# ADIO.net
KiCad netlist of a schematic drawn in Altium Designer
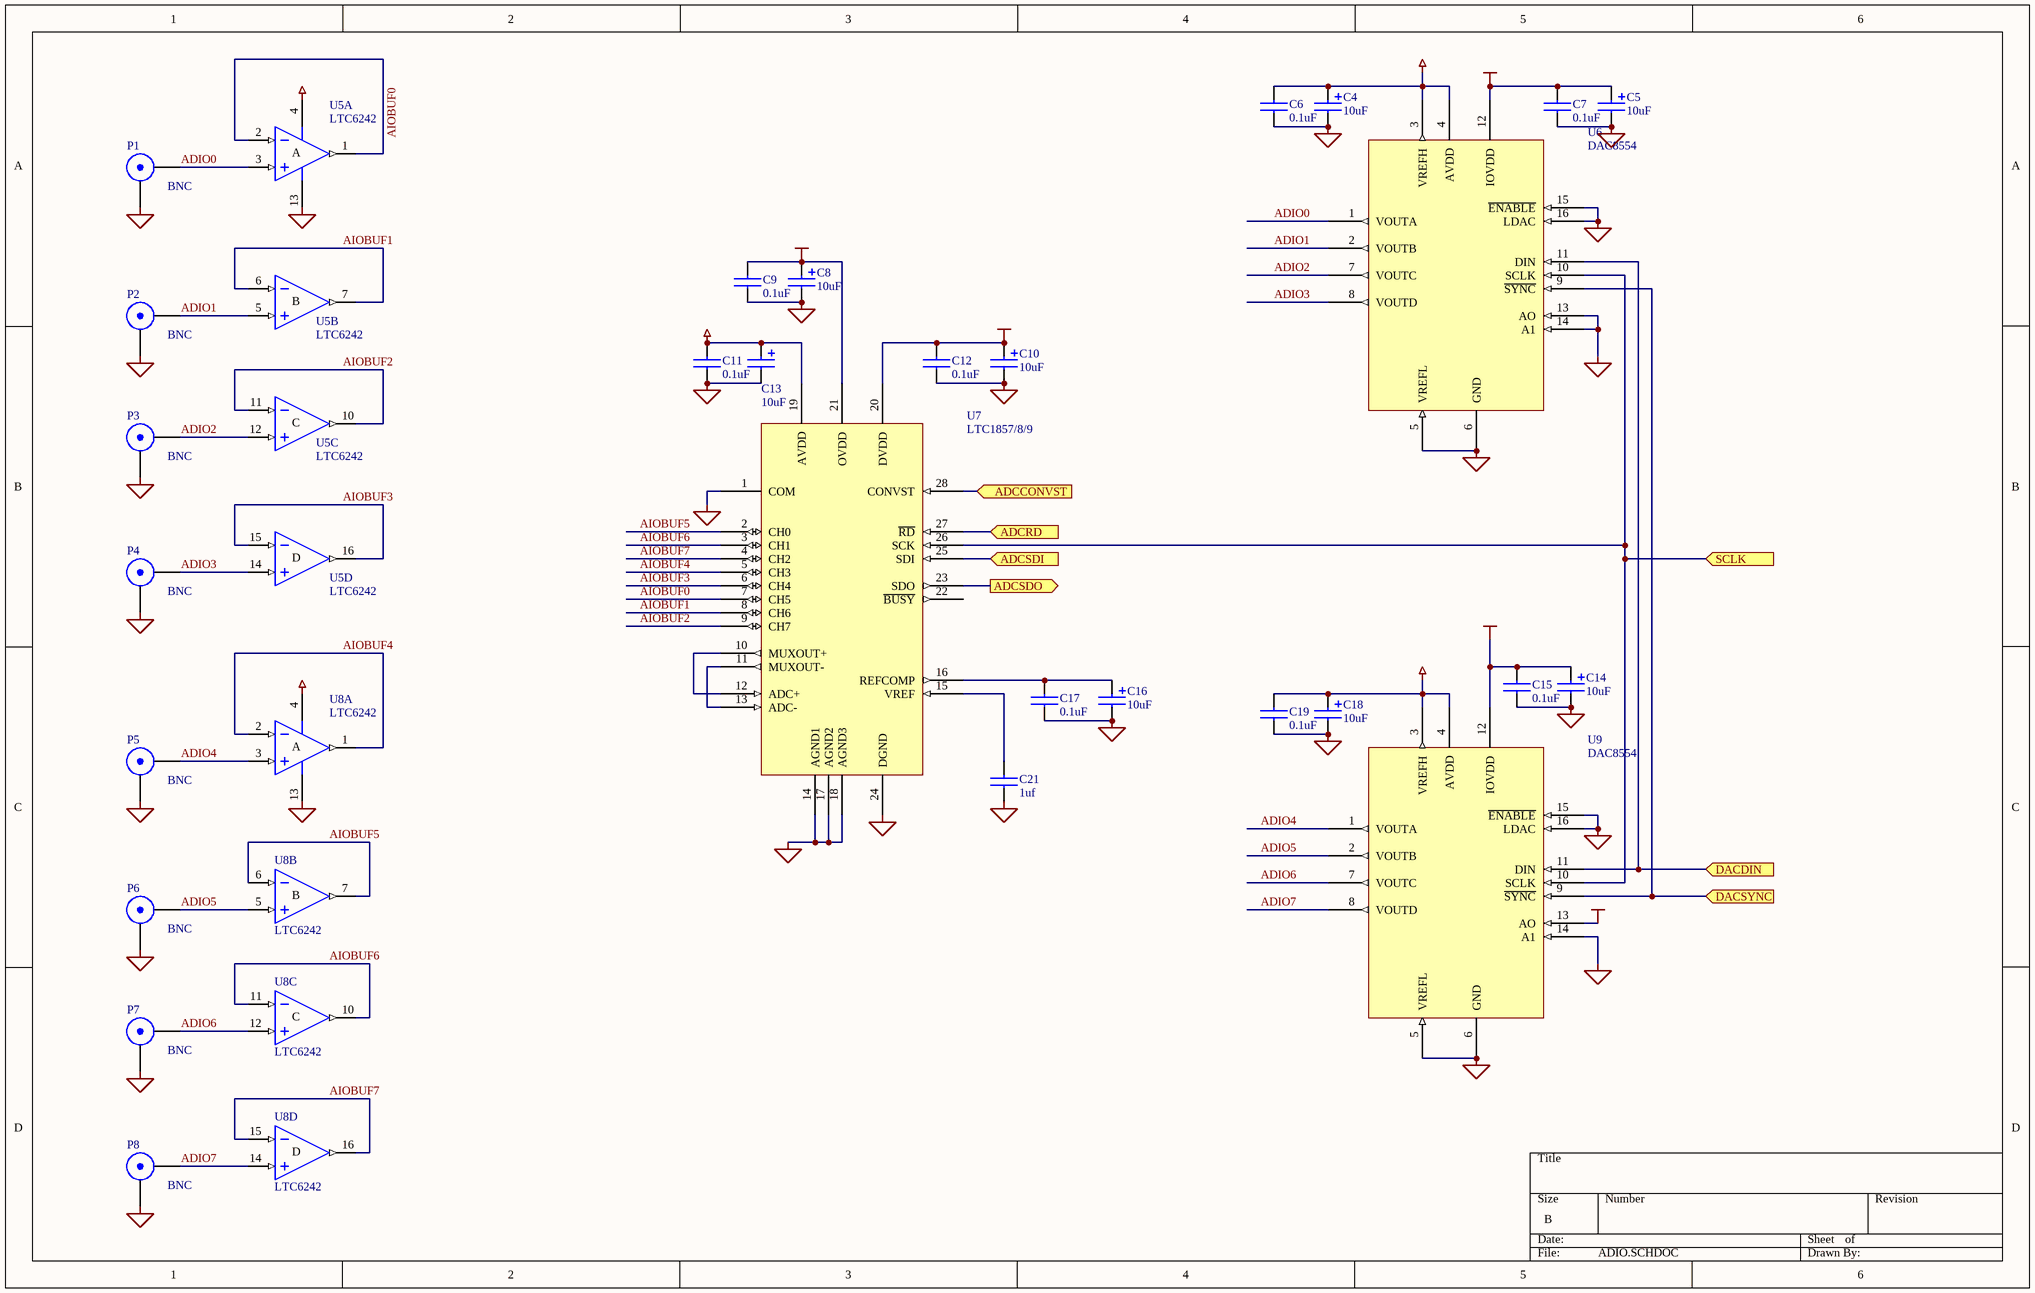
[diagram p0: ADIO.SCHDOC]

(export (version "E")
  (design (tool "Eeschema 10.0.6"))
  (components
    (comp (ref "C4")
      (value "10uF")
      (footprint "3216")
      (description "Standard Capacitor")
      (fields (field (name "Comment") "POLCAP"))
      (libsource (lib "parts") (part "POLCAP"))
    )
    (comp (ref "C5")
      (value "10uF")
      (footprint "3216")
      (description "Standard Capacitor")
      (fields (field (name "Comment") "POLCAP"))
      (libsource (lib "parts") (part "POLCAP"))
    )
    (comp (ref "C6")
      (value "0.1uF")
      (footprint "0603")
      (description "Standard Capacitor")
      (fields (field (name "Comment") "CAPACITOR"))
      (libsource (lib "parts") (part "CAPACITOR"))
    )
    (comp (ref "C7")
      (value "0.1uF")
      (footprint "0603")
      (description "Standard Capacitor")
      (fields (field (name "Comment") "CAPACITOR"))
      (libsource (lib "parts") (part "CAPACITOR"))
    )
    (comp (ref "C8")
      (value "10uF")
      (footprint "3216")
      (description "Standard Capacitor")
      (fields (field (name "Comment") "POLCAP"))
      (libsource (lib "parts") (part "POLCAP"))
    )
    (comp (ref "C9")
      (value "0.1uF")
      (footprint "0603")
      (description "Standard Capacitor")
      (fields (field (name "Comment") "CAPACITOR"))
      (libsource (lib "parts") (part "CAPACITOR"))
    )
    (comp (ref "C10")
      (value "10uF")
      (footprint "3216")
      (description "Standard Capacitor")
      (fields (field (name "Comment") "POLCAP"))
      (libsource (lib "parts") (part "POLCAP"))
    )
    (comp (ref "C11")
      (value "0.1uF")
      (footprint "0603")
      (description "Standard Capacitor")
      (fields (field (name "Comment") "CAPACITOR"))
      (libsource (lib "parts") (part "CAPACITOR"))
    )
    (comp (ref "C12")
      (value "0.1uF")
      (footprint "0603")
      (description "Standard Capacitor")
      (fields (field (name "Comment") "CAPACITOR"))
      (libsource (lib "parts") (part "CAPACITOR"))
    )
    (comp (ref "C13")
      (value "10uF")
      (footprint "3216")
      (description "Standard Capacitor")
      (fields (field (name "Comment") "POLCAP"))
      (libsource (lib "parts") (part "POLCAP"))
    )
    (comp (ref "C14")
      (value "10uF")
      (footprint "3216")
      (description "Standard Capacitor")
      (fields (field (name "Comment") "POLCAP"))
      (libsource (lib "parts") (part "POLCAP"))
    )
    (comp (ref "C15")
      (value "0.1uF")
      (footprint "0603")
      (description "Standard Capacitor")
      (fields (field (name "Comment") "CAPACITOR"))
      (libsource (lib "parts") (part "CAPACITOR"))
    )
    (comp (ref "C16")
      (value "10uF")
      (footprint "3216")
      (description "Standard Capacitor")
      (fields (field (name "Comment") "POLCAP"))
      (libsource (lib "parts") (part "POLCAP"))
    )
    (comp (ref "C17")
      (value "0.1uF")
      (footprint "0603")
      (description "Standard Capacitor")
      (fields (field (name "Comment") "CAPACITOR"))
      (libsource (lib "parts") (part "CAPACITOR"))
    )
    (comp (ref "C18")
      (value "10uF")
      (footprint "3216")
      (description "Standard Capacitor")
      (fields (field (name "Comment") "POLCAP"))
      (libsource (lib "parts") (part "POLCAP"))
    )
    (comp (ref "C19")
      (value "0.1uF")
      (footprint "0603")
      (description "Standard Capacitor")
      (fields (field (name "Comment") "CAPACITOR"))
      (libsource (lib "parts") (part "CAPACITOR"))
    )
    (comp (ref "C21")
      (value "1uf")
      (footprint "0603")
      (description "Standard Capacitor")
      (fields (field (name "Comment") "CAPACITOR"))
      (libsource (lib "parts") (part "CAPACITOR"))
    )
    (comp (ref "P1")
      (value "BNC")
      (footprint "Vertical BNC 227699-1")
      (description "BNC Elbow Connector")
      (fields (field (name "MANUFACTURER") "Generic Components") (field (name "PUBLISHER") "Altium Limited"))
      (libsource (lib "Miscellaneous Connectors") (part "BNC"))
    )
    (comp (ref "P2")
      (value "BNC")
      (footprint "Vertical BNC 227699-1")
      (description "BNC Elbow Connector")
      (fields (field (name "MANUFACTURER") "Generic Components") (field (name "PUBLISHER") "Altium Limited"))
      (libsource (lib "Miscellaneous Connectors") (part "BNC"))
    )
    (comp (ref "P3")
      (value "BNC")
      (footprint "Vertical BNC 227699-1")
      (description "BNC Elbow Connector")
      (fields (field (name "MANUFACTURER") "Generic Components") (field (name "PUBLISHER") "Altium Limited"))
      (libsource (lib "Miscellaneous Connectors") (part "BNC"))
    )
    (comp (ref "P4")
      (value "BNC")
      (footprint "Vertical BNC 227699-1")
      (description "BNC Elbow Connector")
      (fields (field (name "MANUFACTURER") "Generic Components") (field (name "PUBLISHER") "Altium Limited"))
      (libsource (lib "Miscellaneous Connectors") (part "BNC"))
    )
    (comp (ref "P5")
      (value "BNC")
      (footprint "Vertical BNC 227699-1")
      (description "BNC Elbow Connector")
      (fields (field (name "MANUFACTURER") "Generic Components") (field (name "PUBLISHER") "Altium Limited"))
      (libsource (lib "Miscellaneous Connectors") (part "BNC"))
    )
    (comp (ref "P6")
      (value "BNC")
      (footprint "Vertical BNC 227699-1")
      (description "BNC Elbow Connector")
      (fields (field (name "MANUFACTURER") "Generic Components") (field (name "PUBLISHER") "Altium Limited"))
      (libsource (lib "Miscellaneous Connectors") (part "BNC"))
    )
    (comp (ref "P7")
      (value "BNC")
      (footprint "Vertical BNC 227699-1")
      (description "BNC Elbow Connector")
      (fields (field (name "MANUFACTURER") "Generic Components") (field (name "PUBLISHER") "Altium Limited"))
      (libsource (lib "Miscellaneous Connectors") (part "BNC"))
    )
    (comp (ref "P8")
      (value "BNC")
      (footprint "Vertical BNC 227699-1")
      (description "BNC Elbow Connector")
      (fields (field (name "MANUFACTURER") "Generic Components") (field (name "PUBLISHER") "Altium Limited"))
      (libsource (lib "Miscellaneous Connectors") (part "BNC"))
    )
    (comp (ref "U5")
      (value "LTC6242")
      (footprint "LTCDHC-16")
      (description "Quad 18 Mhz, Low Noise, Rail-to-Rail CMOS Op-Amp")
      (fields (field (name "PUBLISHER") "Altium Limited"))
      (libsource (lib "parts") (part "LTC6242"))
    )
    (comp (ref "U6")
      (value "DAC8554")
      (footprint "TSSO5x6-G16")
      (description "TI 16-bit quad chan Voltage Output DAC")
      (libsource (lib "parts") (part "DAC8554"))
    )
    (comp (ref "U7")
      (value "LTC1857/8/9")
      (footprint "LTI_G_TSSOP")
      (description "LTC 8-channel 12, 14, 16 100ksps ADC")
      (libsource (lib "parts") (part "LTC1859"))
    )
    (comp (ref "U8")
      (value "LTC6242")
      (footprint "LTCDHC-16")
      (description "Quad 18 Mhz, Low Noise, Rail-to-Rail CMOS Op-Amp")
      (fields (field (name "PUBLISHER") "Altium Limited"))
      (libsource (lib "parts") (part "LTC6242"))
    )
    (comp (ref "U9")
      (value "DAC8554")
      (footprint "TSSO5x6-G16")
      (description "TI 16-bit quad chan Voltage Output DAC")
      (libsource (lib "parts") (part "DAC8554"))
    )
  )
  (nets
    (net (code "1") (name "+5VCC") (class "Default")
      (node (ref "C10") (pin "1") (pintype "passive"))
      (node (ref "C12") (pin "1") (pintype "passive"))
      (node (ref "U7") (pin "20") (pinfunction "DVDD_20") (pintype "power_in"))
    )
    (net (code "2") (name "/ADCCONVST") (class "Default")
      (node (ref "U7") (pin "28") (pinfunction "CONVST_28") (pintype "input"))
    )
    (net (code "3") (name "/ADCRD") (class "Default")
      (node (ref "U7") (pin "27") (pinfunction "~{RD}_27") (pintype "input"))
    )
    (net (code "4") (name "/ADCSDI") (class "Default")
      (node (ref "U7") (pin "25") (pinfunction "SDI_25") (pintype "input"))
    )
    (net (code "5") (name "/ADCSDO") (class "Default")
      (node (ref "U7") (pin "23") (pinfunction "SDO_23") (pintype "output"))
    )
    (net (code "6") (name "/ADIO0") (class "Default")
      (node (ref "P1") (pin "1") (pinfunction "X_1") (pintype "passive"))
      (node (ref "U5") (pin "3") (pinfunction "IN+_3") (pintype "input"))
      (node (ref "U6") (pin "1") (pinfunction "VOUTA_1") (pintype "output"))
    )
    (net (code "7") (name "/ADIO1") (class "Default")
      (node (ref "P2") (pin "1") (pinfunction "X_1") (pintype "passive"))
      (node (ref "U5") (pin "5") (pinfunction "IN+_5") (pintype "input"))
      (node (ref "U6") (pin "2") (pinfunction "VOUTB_2") (pintype "output"))
    )
    (net (code "8") (name "/ADIO2") (class "Default")
      (node (ref "P3") (pin "1") (pinfunction "X_1") (pintype "passive"))
      (node (ref "U5") (pin "12") (pinfunction "IN+_12") (pintype "input"))
      (node (ref "U6") (pin "7") (pinfunction "VOUTC_7") (pintype "output"))
    )
    (net (code "9") (name "/ADIO3") (class "Default")
      (node (ref "P4") (pin "1") (pinfunction "X_1") (pintype "passive"))
      (node (ref "U5") (pin "14") (pinfunction "IN+_14") (pintype "input"))
      (node (ref "U6") (pin "8") (pinfunction "VOUTD_8") (pintype "output"))
    )
    (net (code "10") (name "/ADIO4") (class "Default")
      (node (ref "P5") (pin "1") (pinfunction "X_1") (pintype "passive"))
      (node (ref "U8") (pin "3") (pinfunction "IN+_3") (pintype "input"))
      (node (ref "U9") (pin "1") (pinfunction "VOUTA_1") (pintype "output"))
    )
    (net (code "11") (name "/ADIO5") (class "Default")
      (node (ref "P6") (pin "1") (pinfunction "X_1") (pintype "passive"))
      (node (ref "U8") (pin "5") (pinfunction "IN+_5") (pintype "input"))
      (node (ref "U9") (pin "2") (pinfunction "VOUTB_2") (pintype "output"))
    )
    (net (code "12") (name "/ADIO6") (class "Default")
      (node (ref "P7") (pin "1") (pinfunction "X_1") (pintype "passive"))
      (node (ref "U8") (pin "12") (pinfunction "IN+_12") (pintype "input"))
      (node (ref "U9") (pin "7") (pinfunction "VOUTC_7") (pintype "output"))
    )
    (net (code "13") (name "/ADIO7") (class "Default")
      (node (ref "P8") (pin "1") (pinfunction "X_1") (pintype "passive"))
      (node (ref "U8") (pin "14") (pinfunction "IN+_14") (pintype "input"))
      (node (ref "U9") (pin "8") (pinfunction "VOUTD_8") (pintype "output"))
    )
    (net (code "14") (name "/AIOBUF0") (class "Default")
      (node (ref "U5") (pin "1") (pinfunction "OUT_1") (pintype "output"))
      (node (ref "U5") (pin "2") (pinfunction "IN-_2") (pintype "input"))
      (node (ref "U7") (pin "7") (pinfunction "CH5_7") (pintype "bidirectional"))
    )
    (net (code "15") (name "/AIOBUF1") (class "Default")
      (node (ref "U5") (pin "6") (pinfunction "IN-_6") (pintype "input"))
      (node (ref "U5") (pin "7") (pinfunction "OUT_7") (pintype "output"))
      (node (ref "U7") (pin "8") (pinfunction "CH6_8") (pintype "bidirectional"))
    )
    (net (code "16") (name "/AIOBUF2") (class "Default")
      (node (ref "U5") (pin "10") (pinfunction "OUT_10") (pintype "output"))
      (node (ref "U5") (pin "11") (pinfunction "IN-_11") (pintype "input"))
      (node (ref "U7") (pin "9") (pinfunction "CH7_9") (pintype "bidirectional"))
    )
    (net (code "17") (name "/AIOBUF3") (class "Default")
      (node (ref "U5") (pin "15") (pinfunction "IN-_15") (pintype "input"))
      (node (ref "U5") (pin "16") (pinfunction "OUT_16") (pintype "output"))
      (node (ref "U7") (pin "6") (pinfunction "CH4_6") (pintype "bidirectional"))
    )
    (net (code "18") (name "/AIOBUF4") (class "Default")
      (node (ref "U7") (pin "5") (pinfunction "CH3_5") (pintype "bidirectional"))
      (node (ref "U8") (pin "1") (pinfunction "OUT_1") (pintype "output"))
      (node (ref "U8") (pin "2") (pinfunction "IN-_2") (pintype "input"))
    )
    (net (code "19") (name "/AIOBUF5") (class "Default")
      (node (ref "U7") (pin "2") (pinfunction "CH0_2") (pintype "bidirectional"))
      (node (ref "U8") (pin "6") (pinfunction "IN-_6") (pintype "input"))
      (node (ref "U8") (pin "7") (pinfunction "OUT_7") (pintype "output"))
    )
    (net (code "20") (name "/AIOBUF6") (class "Default")
      (node (ref "U7") (pin "3") (pinfunction "CH1_3") (pintype "bidirectional"))
      (node (ref "U8") (pin "10") (pinfunction "OUT_10") (pintype "output"))
      (node (ref "U8") (pin "11") (pinfunction "IN-_11") (pintype "input"))
    )
    (net (code "21") (name "/AIOBUF7") (class "Default")
      (node (ref "U7") (pin "4") (pinfunction "CH2_4") (pintype "bidirectional"))
      (node (ref "U8") (pin "15") (pinfunction "IN-_15") (pintype "input"))
      (node (ref "U8") (pin "16") (pinfunction "OUT_16") (pintype "output"))
    )
    (net (code "22") (name "/DACDIN") (class "Default")
      (node (ref "U6") (pin "11") (pinfunction "DIN_11") (pintype "input"))
      (node (ref "U9") (pin "11") (pinfunction "DIN_11") (pintype "input"))
    )
    (net (code "23") (name "/DACSYNC") (class "Default")
      (node (ref "U6") (pin "9") (pinfunction "~{SYNC}_9") (pintype "input"))
      (node (ref "U9") (pin "9") (pinfunction "~{SYNC}_9") (pintype "input"))
    )
    (net (code "24") (name "/SCLK") (class "Default")
      (node (ref "U6") (pin "10") (pinfunction "SCLK_10") (pintype "input"))
      (node (ref "U7") (pin "26") (pinfunction "SCK_26") (pintype "input"))
      (node (ref "U9") (pin "10") (pinfunction "SCLK_10") (pintype "input"))
    )
    (net (code "25") (name "AVDD") (class "Default")
      (node (ref "C11") (pin "1") (pintype "passive"))
      (node (ref "C13") (pin "1") (pintype "passive"))
      (node (ref "C18") (pin "1") (pintype "passive"))
      (node (ref "C19") (pin "1") (pintype "passive"))
      (node (ref "C4") (pin "1") (pintype "passive"))
      (node (ref "C6") (pin "1") (pintype "passive"))
      (node (ref "U5") (pin "4") (pinfunction "V+_4") (pintype "power_in"))
      (node (ref "U6") (pin "3") (pinfunction "VREFH_3") (pintype "output"))
      (node (ref "U6") (pin "4") (pinfunction "AVDD_4") (pintype "power_in"))
      (node (ref "U7") (pin "19") (pinfunction "AVDD_19") (pintype "power_in"))
      (node (ref "U8") (pin "4") (pinfunction "V+_4") (pintype "power_in"))
      (node (ref "U9") (pin "3") (pinfunction "VREFH_3") (pintype "output"))
      (node (ref "U9") (pin "4") (pinfunction "AVDD_4") (pintype "power_in"))
    )
    (net (code "26") (name "GND") (class "Default")
      (node (ref "C10") (pin "2") (pintype "passive"))
      (node (ref "C11") (pin "2") (pintype "passive"))
      (node (ref "C12") (pin "2") (pintype "passive"))
      (node (ref "C13") (pin "2") (pintype "passive"))
      (node (ref "C14") (pin "2") (pintype "passive"))
      (node (ref "C15") (pin "2") (pintype "passive"))
      (node (ref "C16") (pin "2") (pintype "passive"))
      (node (ref "C17") (pin "2") (pintype "passive"))
      (node (ref "C18") (pin "2") (pintype "passive"))
      (node (ref "C19") (pin "2") (pintype "passive"))
      (node (ref "C21") (pin "2") (pintype "passive"))
      (node (ref "C4") (pin "2") (pintype "passive"))
      (node (ref "C5") (pin "2") (pintype "passive"))
      (node (ref "C6") (pin "2") (pintype "passive"))
      (node (ref "C7") (pin "2") (pintype "passive"))
      (node (ref "C8") (pin "2") (pintype "passive"))
      (node (ref "C9") (pin "2") (pintype "passive"))
      (node (ref "P1") (pin "2") (pinfunction "Y_2") (pintype "passive"))
      (node (ref "P2") (pin "2") (pinfunction "Y_2") (pintype "passive"))
      (node (ref "P3") (pin "2") (pinfunction "Y_2") (pintype "passive"))
      (node (ref "P4") (pin "2") (pinfunction "Y_2") (pintype "passive"))
      (node (ref "P5") (pin "2") (pinfunction "Y_2") (pintype "passive"))
      (node (ref "P6") (pin "2") (pinfunction "Y_2") (pintype "passive"))
      (node (ref "P7") (pin "2") (pinfunction "Y_2") (pintype "passive"))
      (node (ref "P8") (pin "2") (pinfunction "Y_2") (pintype "passive"))
      (node (ref "U5") (pin "13") (pinfunction "V-_13") (pintype "power_in"))
      (node (ref "U6") (pin "13") (pinfunction "AO_13") (pintype "input"))
      (node (ref "U6") (pin "14") (pinfunction "A1_14") (pintype "input"))
      (node (ref "U6") (pin "15") (pinfunction "~{ENABLE}_15") (pintype "input"))
      (node (ref "U6") (pin "16") (pinfunction "LDAC_16") (pintype "input"))
      (node (ref "U6") (pin "5") (pinfunction "VREFL_5") (pintype "input"))
      (node (ref "U6") (pin "6") (pinfunction "GND_6") (pintype "power_in"))
      (node (ref "U7") (pin "1") (pinfunction "COM_1") (pintype "power_in"))
      (node (ref "U7") (pin "14") (pinfunction "AGND1_14") (pintype "power_in"))
      (node (ref "U7") (pin "17") (pinfunction "AGND2_17") (pintype "power_in"))
      (node (ref "U7") (pin "18") (pinfunction "AGND3_18") (pintype "power_in"))
      (node (ref "U7") (pin "24") (pinfunction "DGND_24") (pintype "power_in"))
      (node (ref "U8") (pin "13") (pinfunction "V-_13") (pintype "power_in"))
      (node (ref "U9") (pin "14") (pinfunction "A1_14") (pintype "input"))
      (node (ref "U9") (pin "15") (pinfunction "~{ENABLE}_15") (pintype "input"))
      (node (ref "U9") (pin "16") (pinfunction "LDAC_16") (pintype "input"))
      (node (ref "U9") (pin "5") (pinfunction "VREFL_5") (pintype "input"))
      (node (ref "U9") (pin "6") (pinfunction "GND_6") (pintype "power_in"))
    )
    (net (code "27") (name "Net-(U7-ADC+)") (class "Default")
      (node (ref "U7") (pin "10") (pinfunction "MUXOUT+_10") (pintype "output"))
      (node (ref "U7") (pin "12") (pinfunction "ADC+_12") (pintype "input"))
    )
    (net (code "28") (name "Net-(U7-ADC-)") (class "Default")
      (node (ref "U7") (pin "11") (pinfunction "MUXOUT-_11") (pintype "output"))
      (node (ref "U7") (pin "13") (pinfunction "ADC-_13") (pintype "input"))
    )
    (net (code "29") (name "Net-(U7-REFCOMP)") (class "Default")
      (node (ref "C16") (pin "1") (pintype "passive"))
      (node (ref "C17") (pin "1") (pintype "passive"))
      (node (ref "U7") (pin "16") (pinfunction "REFCOMP_16") (pintype "output"))
    )
    (net (code "30") (name "Net-(U7-VREF)") (class "Default")
      (node (ref "C21") (pin "1") (pintype "passive"))
      (node (ref "U7") (pin "15") (pinfunction "VREF_15") (pintype "input"))
    )
    (net (code "31") (name "VCC") (class "Default")
      (node (ref "C14") (pin "1") (pintype "passive"))
      (node (ref "C15") (pin "1") (pintype "passive"))
      (node (ref "C5") (pin "1") (pintype "passive"))
      (node (ref "C7") (pin "1") (pintype "passive"))
      (node (ref "C8") (pin "1") (pintype "passive"))
      (node (ref "C9") (pin "1") (pintype "passive"))
      (node (ref "U6") (pin "12") (pinfunction "IOVDD_12") (pintype "power_in"))
      (node (ref "U7") (pin "21") (pinfunction "OVDD_21") (pintype "power_in"))
      (node (ref "U9") (pin "12") (pinfunction "IOVDD_12") (pintype "power_in"))
      (node (ref "U9") (pin "13") (pinfunction "AO_13") (pintype "input"))
    )
    (net (code "32") (name "unconnected-(U7-~{BUSY}-Pad22)") (class "Default")
      (node (ref "U7") (pin "22") (pinfunction "~{BUSY}_22") (pintype "output"))
    )
  )
)
